# USB_mega.net
KiCad netlist of a schematic drawn in Altium Designer
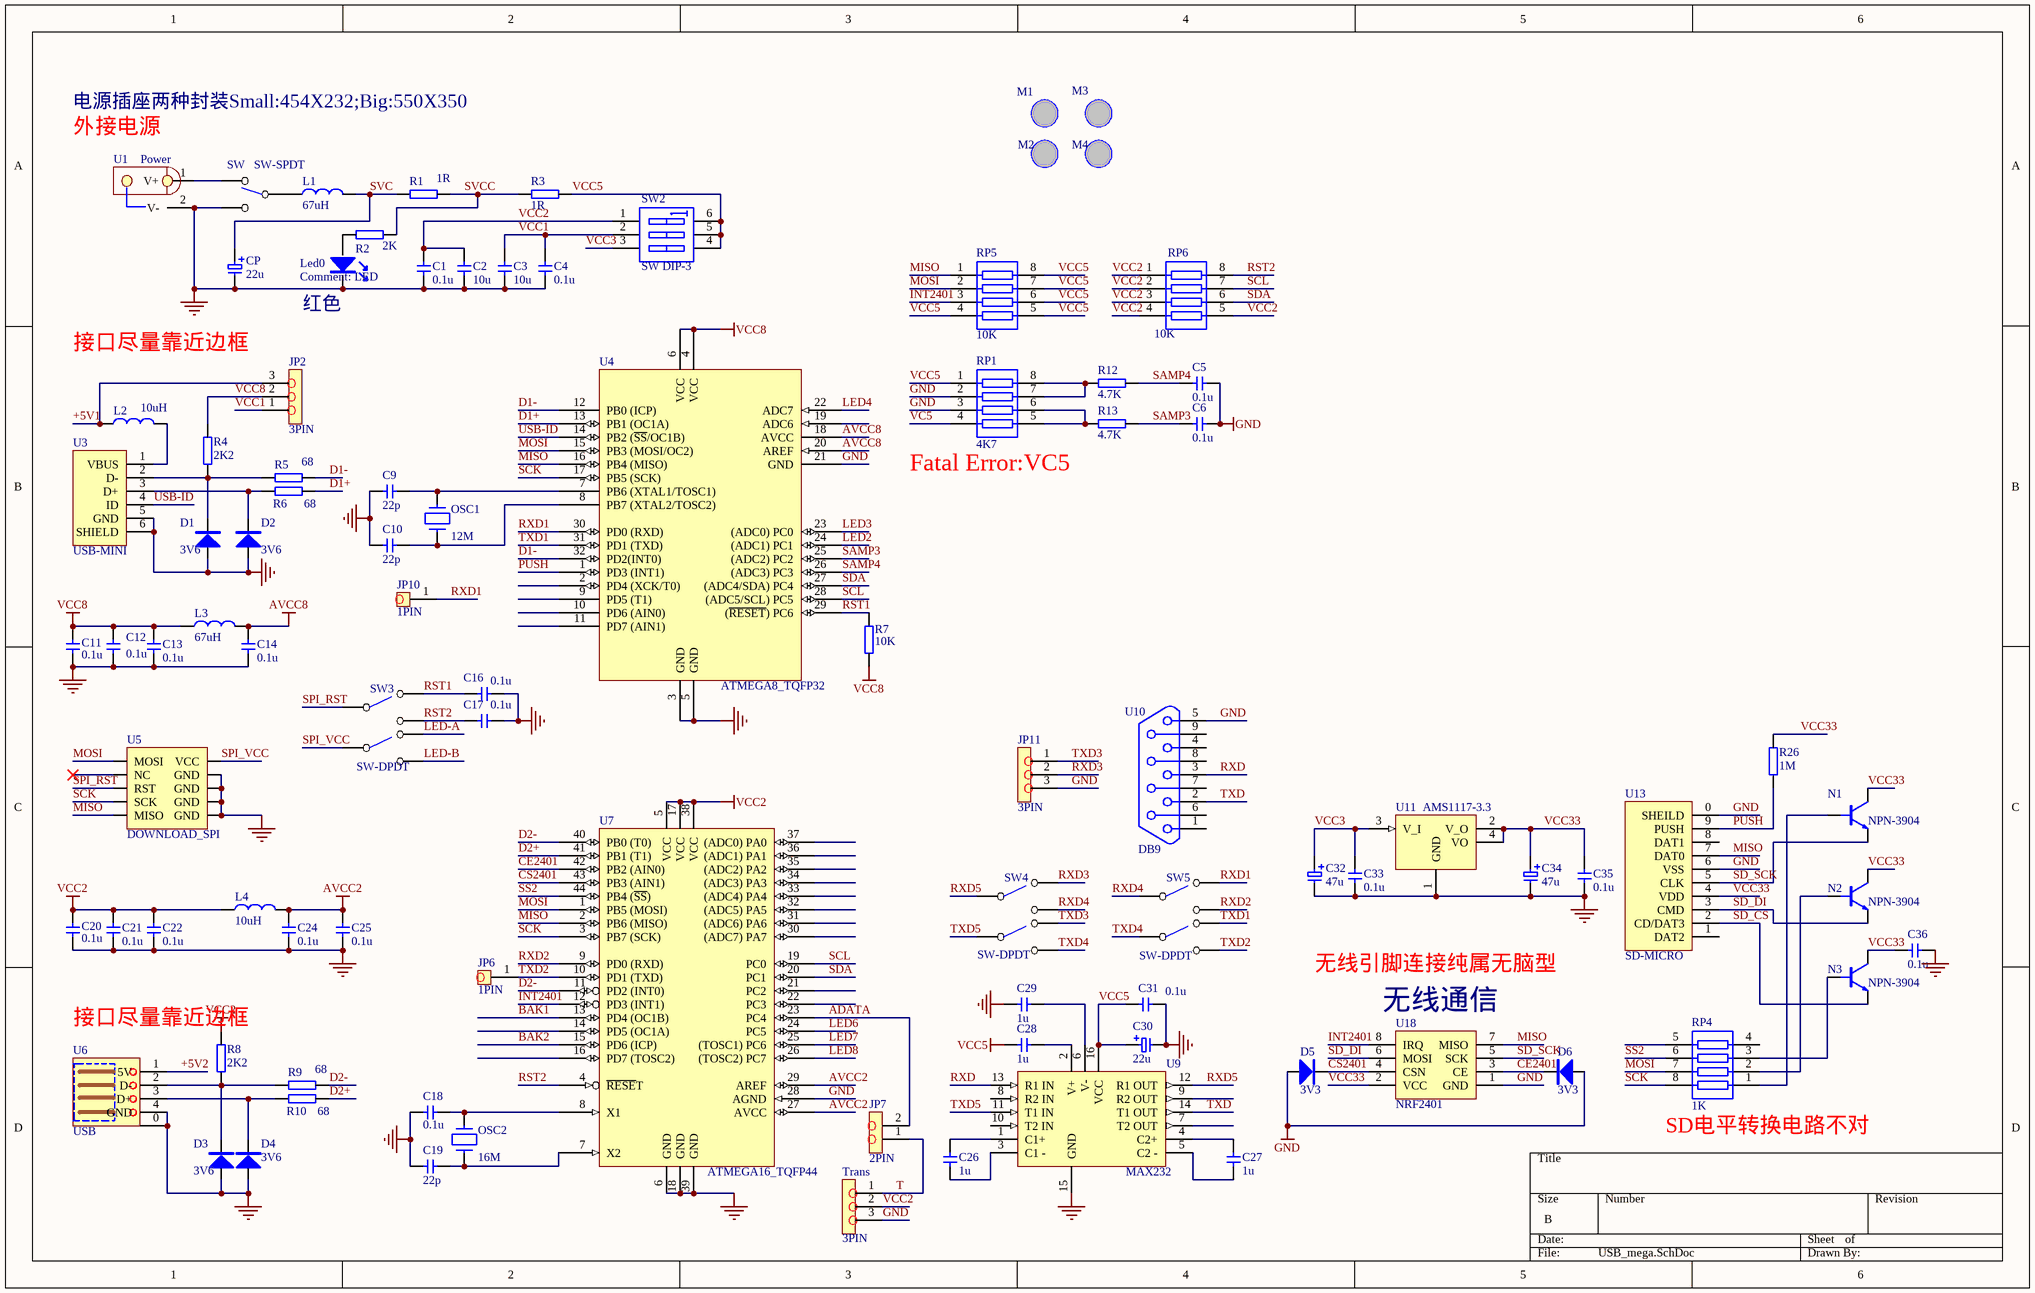
[diagram p0: USB_mega.SchDoc]

(export (version "E")
  (design (tool "Eeschema 10.0.6"))
  (components
    (comp (ref "C1") (value "0.1u") (footprint "0805") (libsource (lib "*") (part "CAPA")))
    (comp (ref "C2") (value "10u") (footprint "0805") (libsource (lib "*") (part "CAPA")))
    (comp (ref "C3") (value "10u") (footprint "0805") (libsource (lib "*") (part "CAPA")))
    (comp (ref "C4") (value "0.1u") (footprint "0805") (libsource (lib "*") (part "CAPA")))
    (comp (ref "C5") (value "0.1u") (footprint "RC100") (libsource (lib "*") (part "CAPA")))
    (comp (ref "C6") (value "0.1u") (footprint "RC100") (libsource (lib "*") (part "CAPA")))
    (comp (ref "C9") (value "22p") (footprint "RC80") (libsource (lib "*") (part "CAPA")))
    (comp (ref "C10") (value "22p") (footprint "RC80") (libsource (lib "*") (part "CAPA")))
    (comp (ref "C11") (value "0.1u") (footprint "0805") (libsource (lib "*") (part "CAPA")))
    (comp (ref "C12") (value "0.1u") (footprint "0805") (libsource (lib "*") (part "CAPA")))
    (comp (ref "C13") (value "0.1u") (footprint "0805") (libsource (lib "*") (part "CAPA")))
    (comp (ref "C14") (value "0.1u") (footprint "0805") (libsource (lib "*") (part "CAPA")))
    (comp (ref "C16") (value "0.1u") (footprint "0805") (libsource (lib "*") (part "CAPA")))
    (comp (ref "C17") (value "0.1u") (footprint "0805") (libsource (lib "*") (part "CAPA")))
    (comp (ref "C18") (value "0.1u") (footprint "RC80") (libsource (lib "*") (part "CAPA")))
    (comp (ref "C19") (value "22p") (footprint "RC80") (libsource (lib "*") (part "CAPA")))
    (comp (ref "C20") (value "0.1u") (footprint "0805") (libsource (lib "*") (part "CAPA")))
    (comp (ref "C21") (value "0.1u") (footprint "0805") (libsource (lib "*") (part "CAPA")))
    (comp (ref "C22") (value "0.1u") (footprint "0805") (libsource (lib "*") (part "CAPA")))
    (comp (ref "C24") (value "0.1u") (footprint "0805") (libsource (lib "*") (part "CAPA")))
    (comp (ref "C25") (value "0.1u") (footprint "0805") (libsource (lib "*") (part "CAPA")))
    (comp (ref "C26") (value "1u") (footprint "0805") (libsource (lib "*") (part "CAPA")))
    (comp (ref "C27") (value "1u") (footprint "0805") (libsource (lib "*") (part "CAPA")))
    (comp (ref "C28") (value "1u") (footprint "0805") (libsource (lib "*") (part "CAPA")))
    (comp (ref "C29") (value "1u") (footprint "0805") (libsource (lib "*") (part "CAPA")))
    (comp (ref "C30") (value "22u") (footprint "CP+140") (libsource (lib "*") (part "CAP+")))
    (comp (ref "C31") (value "0.1u") (footprint "0805") (libsource (lib "*") (part "CAPA")))
    (comp (ref "C32") (value "47u") (footprint "CP+140") (libsource (lib "*") (part "CAP+")))
    (comp (ref "C33") (value "0.1u") (footprint "0805") (libsource (lib "*") (part "CAPA")))
    (comp (ref "C34") (value "47u") (footprint "CP+140") (libsource (lib "*") (part "CAP+")))
    (comp (ref "C35") (value "0.1u") (footprint "0805") (libsource (lib "*") (part "CAPA")))
    (comp (ref "C36") (value "0.1u") (footprint "0805") (libsource (lib "*") (part "CAPA")))
    (comp (ref "CP") (value "22u") (footprint "CP+140") (libsource (lib "*") (part "CAP+")))
    (comp (ref "D1") (value "3V6") (footprint "DC140") (libsource (lib "*") (part "DIODE")))
    (comp (ref "D2") (value "3V6") (footprint "DC140") (libsource (lib "*") (part "DIODE")))
    (comp (ref "D3") (value "3V6") (footprint "DC140") (libsource (lib "*") (part "DIODE")))
    (comp (ref "D4") (value "3V6") (footprint "DC140") (libsource (lib "*") (part "DIODE")))
    (comp (ref "D5") (value "3V3") (footprint "DC200") (libsource (lib "*") (part "DIODE")))
    (comp (ref "D6") (value "3V3") (footprint "DC200") (libsource (lib "*") (part "DIODE")))
    (comp (ref "JP2") (value "3PIN") (footprint "SIP3") (libsource (lib "") (part "3PIN_1")))
    (comp (ref "JP6") (value "1PIN") (footprint "SIP1") (libsource (lib "*") (part "1PIN")))
    (comp (ref "JP7") (value "2PIN") (footprint "SIP2") (libsource (lib "*") (part "2PIN")))
    (comp (ref "JP10") (value "1PIN") (footprint "SIP1") (libsource (lib "*") (part "1PIN")))
    (comp (ref "JP11") (value "3PIN") (footprint "SIP3") (libsource (lib "*") (part "3PIN")))
    (comp (ref "L1") (value "67uH") (footprint "1206") (libsource (lib "*") (part "LH")))
    (comp (ref "L2") (value "10uH") (footprint "0805") (libsource (lib "*") (part "LH")))
    (comp (ref "L3") (value "67uH") (footprint "1206") (libsource (lib "*") (part "LH")))
    (comp (ref "L4") (value "10uH") (footprint "0805") (libsource (lib "*") (part "LH")))
    (comp (ref "Led0") (value "LED") (footprint "LED100") (libsource (lib "*") (part "LED")))
    (comp (ref "M1") (value "M3") (footprint "M3") (libsource (lib "*") (part "M3")))
    (comp (ref "M2") (value "M3") (footprint "M3") (libsource (lib "*") (part "M3")))
    (comp (ref "M3") (value "M3") (footprint "M3") (libsource (lib "*") (part "M3")))
    (comp (ref "M4") (value "M3") (footprint "M3") (libsource (lib "*") (part "M3")))
    (comp (ref "N1") (value "NPN-3904") (footprint "SOT-23A") (libsource (lib "*") (part "NPN-A")))
    (comp (ref "N2") (value "NPN-3904") (footprint "SOT-23A") (libsource (lib "*") (part "NPN-A")))
    (comp (ref "N3") (value "NPN-3904") (footprint "SOT-23A") (libsource (lib "*") (part "NPN-A")))
    (comp (ref "OSC1") (value "12M") (footprint "OSC200") (libsource (lib "*") (part "CRYSTAL")))
    (comp (ref "OSC2") (value "16M") (footprint "OSC200") (libsource (lib "*") (part "CRYSTAL")))
    (comp (ref "R1") (value "1R") (footprint "0805") (libsource (lib "*") (part "RES2A")))
    (comp (ref "R2") (value "2K") (footprint "0805") (libsource (lib "*") (part "RES2A")))
    (comp (ref "R3") (value "1R") (footprint "0805") (libsource (lib "*") (part "RES2A")))
    (comp (ref "R4") (value "2K2") (footprint "0805") (libsource (lib "*") (part "RES2A")))
    (comp (ref "R5") (value "68") (footprint "0805") (libsource (lib "*") (part "RES2A")))
    (comp (ref "R6") (value "68") (footprint "0805") (libsource (lib "*") (part "RES2A")))
    (comp (ref "R7") (value "10K") (footprint "0805") (libsource (lib "*") (part "RES2A")))
    (comp (ref "R8") (value "2K2") (footprint "0805") (libsource (lib "*") (part "RES2A")))
    (comp (ref "R9") (value "68") (footprint "0805") (libsource (lib "*") (part "RES2A")))
    (comp (ref "R10") (value "68") (footprint "0805") (libsource (lib "*") (part "RES2A")))
    (comp (ref "R12") (value "4.7K") (footprint "0805") (libsource (lib "*") (part "RES2A")))
    (comp (ref "R13") (value "4.7K") (footprint "0805") (libsource (lib "*") (part "RES2A")))
    (comp (ref "R26") (value "1M") (footprint "0805") (libsource (lib "*") (part "RES2A")))
    (comp (ref "RP1") (value "4K7") (footprint "RN4") (libsource (lib "*") (part "RESPACK4")))
    (comp (ref "RP4") (value "1K") (footprint "RN4") (libsource (lib "*") (part "RESPACK4")))
    (comp (ref "RP5") (value "10K") (footprint "RN4") (libsource (lib "*") (part "RESPACK4")))
    (comp (ref "RP6") (value "10K") (footprint "RN4") (libsource (lib "*") (part "RESPACK4")))
    (comp (ref "SW") (value "SW-SPDT") (footprint "SW-SPDT") (libsource (lib "*") (part "SW-SPDT")))
    (comp (ref "SW2")
      (value "SW DIP-3")
      (footprint "SW-DIP3")
      (description "DIP Switch")
      (libsource (lib "*") (part "SW DIP-3"))
    )
    (comp (ref "SW3") (value "SW-DPDT") (footprint "SW-DPDT") (libsource (lib "*") (part "SW-DPDT")))
    (comp (ref "SW4") (value "SW-DPDT") (footprint "SW-DPDT") (libsource (lib "*") (part "SW-DPDT")))
    (comp (ref "SW5") (value "SW-DPDT") (footprint "SW-DPDT") (libsource (lib "*") (part "SW-DPDT")))
    (comp (ref "Trans") (value "3PIN") (footprint "SIP3") (libsource (lib "*") (part "3PIN")))
    (comp (ref "U1") (value "Power") (footprint "POWER_BIG") (libsource (lib "*") (part "POWER")))
    (comp (ref "U3") (value "USB-MINI") (footprint "USB-MINI-R") (libsource (lib "*") (part "USB-MINI")))
    (comp (ref "U4")
      (value "ATMEGA8_TQFP32")
      (footprint "TQFP-32")
      (description "Atmel Microcontroller - Library created by carel..  <www.mpfreezone.com>")
      (libsource (lib "*") (part "ATMEGA8_TQFP32"))
    )
    (comp (ref "U5")
      (value "DOWNLOAD_SPI")
      (footprint "DOWNLOAD")
      (libsource (lib "*") (part "DOWNLOAD_SPI"))
    )
    (comp (ref "U6") (value "USB") (footprint "USB-A-R") (libsource (lib "*") (part "USB")))
    (comp (ref "U7")
      (value "ATMEGA16_TQFP44")
      (footprint "TQFP-44")
      (description "Atmel Microcontroller - Library created by carel..  <www.mpfreezone.com>")
      (libsource (lib "*") (part "AT90S8535_TQFP44"))
    )
    (comp (ref "U9") (value "MAX232") (footprint "SO-16") (libsource (lib "*") (part "MAX232")))
    (comp (ref "U10") (value "DB9") (footprint "DB-9RA/F") (libsource (lib "*") (part "DB9")))
    (comp (ref "U11") (value "AMS1117-3.3") (footprint "SOT-223") (libsource (lib "*") (part "VOTAGE_V33")))
    (comp (ref "U13") (value "SD-MICRO") (footprint "TF-2") (libsource (lib "*") (part "SD-MICRO")))
    (comp (ref "U18") (value "NRF2401") (footprint "NRF2401") (libsource (lib "*") (part "NRF2401")))
  )
  (nets
    (net (code "1") (name "/+5V1") (class "Default")
      (node (ref "JP2") (pin "3") (pintype "passive"))
      (node (ref "L2") (pin "1") (pintype "passive"))
    )
    (net (code "2") (name "/+5V2") (class "Default")
      (node (ref "U6") (pin "1") (pinfunction "5V_1") (pintype "passive"))
    )
    (net (code "4") (name "/ADATA") (class "Default")
      (node (ref "JP7") (pin "2") (pintype "passive"))
      (node (ref "U7") (pin "23") (pinfunction "PC4_23") (pintype "bidirectional"))
    )
    (net (code "5") (name "/BAK1") (class "Default")
      (node (ref "U7") (pin "13") (pinfunction "PD4_(OC1B)_13") (pintype "bidirectional"))
    )
    (net (code "6") (name "/BAK2") (class "Default")
      (node (ref "U7") (pin "15") (pinfunction "PD6_(ICP)_15") (pintype "bidirectional"))
    )
    (net (code "7") (name "/CE2401") (class "Default")
      (node (ref "D6") (pin "K") (pintype "passive"))
      (node (ref "U18") (pin "3") (pinfunction "CE_3") (pintype "passive"))
      (node (ref "U7") (pin "42") (pinfunction "PB2_(AIN0)_42") (pintype "bidirectional"))
    )
    (net (code "8") (name "/CS2401") (class "Default")
      (node (ref "D5") (pin "K") (pintype "passive"))
      (node (ref "U18") (pin "4") (pinfunction "CSN_4") (pintype "passive"))
      (node (ref "U7") (pin "43") (pinfunction "PB3_(AIN1)_43") (pintype "bidirectional"))
    )
    (net (code "9") (name "/D1+") (class "Default")
      (node (ref "R6") (pin "2") (pintype "passive"))
      (node (ref "U4") (pin "13") (pinfunction "PB1_(OC1A)_13") (pintype "bidirectional"))
    )
    (net (code "10") (name "/D1-") (class "Default")
      (node (ref "R5") (pin "2") (pintype "passive"))
      (node (ref "U4") (pin "12") (pinfunction "PB0_(ICP)_12") (pintype "passive"))
      (node (ref "U4") (pin "32") (pinfunction "PD2(INT0)_32") (pintype "bidirectional"))
    )
    (net (code "11") (name "/D2+") (class "Default")
      (node (ref "R10") (pin "2") (pintype "passive"))
      (node (ref "U7") (pin "41") (pinfunction "PB1_(T1)_41") (pintype "bidirectional"))
    )
    (net (code "12") (name "/D2-") (class "Default")
      (node (ref "R9") (pin "2") (pintype "passive"))
      (node (ref "U7") (pin "11") (pinfunction "PD2_(INT0)_11") (pintype "bidirectional"))
      (node (ref "U7") (pin "40") (pinfunction "PB0_(T0)_40") (pintype "bidirectional"))
    )
    (net (code "13") (name "/INT2401") (class "Default")
      (node (ref "RP5") (pin "3") (pintype "passive"))
      (node (ref "U18") (pin "8") (pinfunction "IRQ_8") (pintype "passive"))
      (node (ref "U7") (pin "12") (pinfunction "PD3_(INT1)_12") (pintype "bidirectional"))
    )
    (net (code "14") (name "/LED-A") (class "Default") (node (ref "SW3") (pin "5") (pintype "passive")))
    (net (code "15") (name "/LED-B") (class "Default") (node (ref "SW3") (pin "6") (pintype "passive")))
    (net (code "16") (name "/LED2") (class "Default")
      (node (ref "U4") (pin "24") (pinfunction "(ADC1)_PC1_24") (pintype "bidirectional"))
    )
    (net (code "17") (name "/LED3") (class "Default")
      (node (ref "U4") (pin "23") (pinfunction "(ADC0)_PC0_23") (pintype "bidirectional"))
    )
    (net (code "18") (name "/LED4") (class "Default")
      (node (ref "U4") (pin "22") (pinfunction "ADC7_22") (pintype "input"))
    )
    (net (code "19") (name "/LED6") (class "Default")
      (node (ref "U7") (pin "24") (pinfunction "PC5_24") (pintype "bidirectional"))
    )
    (net (code "20") (name "/LED7") (class "Default")
      (node (ref "U7") (pin "25") (pinfunction "(TOSC1)_PC6_25") (pintype "bidirectional"))
    )
    (net (code "21") (name "/LED8") (class "Default")
      (node (ref "U7") (pin "26") (pinfunction "(TOSC2)_PC7_26") (pintype "bidirectional"))
    )
    (net (code "22") (name "/MISO") (class "Default")
      (node (ref "RP5") (pin "1") (pintype "passive"))
      (node (ref "U13") (pin "7") (pinfunction "DAT0_7") (pintype "passive"))
      (node (ref "U18") (pin "7") (pinfunction "MISO_7") (pintype "passive"))
      (node (ref "U4") (pin "16") (pinfunction "PB4_(MISO)_16") (pintype "bidirectional"))
      (node (ref "U5") (pin "9") (pinfunction "MISO_9") (pintype "passive"))
      (node (ref "U7") (pin "2") (pinfunction "PB6_(MISO)_2") (pintype "bidirectional"))
    )
    (net (code "23") (name "/MOSI") (class "Default")
      (node (ref "RP4") (pin "7") (pintype "passive"))
      (node (ref "RP5") (pin "2") (pintype "passive"))
      (node (ref "U4") (pin "15") (pinfunction "PB3_(MOSI/OC2)_15") (pintype "bidirectional"))
      (node (ref "U5") (pin "1") (pinfunction "MOSI_1") (pintype "passive"))
      (node (ref "U7") (pin "1") (pinfunction "PB5_(MOSI)_1") (pintype "bidirectional"))
    )
    (net (code "24") (name "/PUSH") (class "Default")
      (node (ref "R26") (pin "1") (pintype "passive"))
      (node (ref "U13") (pin "9") (pinfunction "PUSH_9") (pintype "passive"))
      (node (ref "U4") (pin "1") (pinfunction "PD3_(INT1)_1") (pintype "bidirectional"))
    )
    (net (code "25") (name "/RST1") (class "Default")
      (node (ref "C16") (pin "2") (pintype "passive"))
      (node (ref "R7") (pin "1") (pintype "passive"))
      (node (ref "SW3") (pin "2") (pintype "passive"))
      (node (ref "U4") (pin "29") (pinfunction "(~{RESET})_PC6_29") (pintype "bidirectional"))
    )
    (net (code "26") (name "/RST2") (class "Default")
      (node (ref "C17") (pin "2") (pintype "passive"))
      (node (ref "RP6") (pin "8") (pintype "passive"))
      (node (ref "SW3") (pin "3") (pintype "passive"))
      (node (ref "U7") (pin "4") (pinfunction "~{RESE}T_4") (pintype "input"))
    )
    (net (code "27") (name "/RXD") (class "Default")
      (node (ref "U10") (pin "3") (pinfunction "3_3") (pintype "passive"))
      (node (ref "U9") (pin "13") (pinfunction "R1_IN_13") (pintype "input"))
    )
    (net (code "28") (name "/RXD1") (class "Default")
      (node (ref "JP10") (pin "1") (pintype "passive"))
      (node (ref "SW5") (pin "2") (pintype "passive"))
      (node (ref "U4") (pin "30") (pinfunction "PD0_(RXD)_30") (pintype "bidirectional"))
    )
    (net (code "29") (name "/RXD2") (class "Default")
      (node (ref "SW5") (pin "3") (pintype "passive"))
      (node (ref "U7") (pin "9") (pinfunction "PD0_(RXD)_9") (pintype "bidirectional"))
    )
    (net (code "30") (name "/RXD3") (class "Default")
      (node (ref "JP11") (pin "2") (pintype "passive"))
      (node (ref "SW4") (pin "2") (pintype "passive"))
    )
    (net (code "31") (name "/RXD4") (class "Default")
      (node (ref "SW4") (pin "3") (pintype "passive"))
      (node (ref "SW5") (pin "1") (pintype "passive"))
    )
    (net (code "32") (name "/RXD5") (class "Default")
      (node (ref "SW4") (pin "1") (pintype "passive"))
      (node (ref "U9") (pin "12") (pinfunction "R1_OUT_12") (pintype "output"))
    )
    (net (code "33") (name "/SAMP3") (class "Default")
      (node (ref "C6") (pin "1") (pintype "passive"))
      (node (ref "R13") (pin "2") (pintype "passive"))
      (node (ref "U4") (pin "25") (pinfunction "(ADC2)_PC2_25") (pintype "bidirectional"))
    )
    (net (code "34") (name "/SAMP4") (class "Default")
      (node (ref "C5") (pin "1") (pintype "passive"))
      (node (ref "R12") (pin "2") (pintype "passive"))
      (node (ref "U4") (pin "26") (pinfunction "(ADC3)_PC3_26") (pintype "bidirectional"))
    )
    (net (code "35") (name "/SCK") (class "Default")
      (node (ref "RP4") (pin "8") (pintype "passive"))
      (node (ref "U4") (pin "17") (pinfunction "PB5_(SCK)_17") (pintype "bidirectional"))
      (node (ref "U5") (pin "7") (pinfunction "SCK_7") (pintype "passive"))
      (node (ref "U7") (pin "3") (pinfunction "PB7_(SCK)_3") (pintype "bidirectional"))
    )
    (net (code "36") (name "/SCL") (class "Default")
      (node (ref "RP6") (pin "7") (pintype "passive"))
      (node (ref "U4") (pin "28") (pinfunction "(ADC5/SCL)_PC5_28") (pintype "bidirectional"))
      (node (ref "U7") (pin "19") (pinfunction "PC0_19") (pintype "bidirectional"))
    )
    (net (code "37") (name "/SDA") (class "Default")
      (node (ref "RP6") (pin "6") (pintype "passive"))
      (node (ref "U4") (pin "27") (pinfunction "(ADC4/SDA)_PC4_27") (pintype "bidirectional"))
      (node (ref "U7") (pin "20") (pinfunction "PC1_20") (pintype "bidirectional"))
    )
    (net (code "38") (name "/SD_CS") (class "Default")
      (node (ref "N3") (pin "E") (pintype "passive"))
      (node (ref "U13") (pin "2") (pinfunction "CD/DAT3_2") (pintype "passive"))
    )
    (net (code "39") (name "/SD_DI") (class "Default")
      (node (ref "N2") (pin "E") (pintype "passive"))
      (node (ref "U13") (pin "3") (pinfunction "CMD_3") (pintype "passive"))
      (node (ref "U18") (pin "6") (pinfunction "MOSI_6") (pintype "passive"))
    )
    (net (code "40") (name "/SD_SCK") (class "Default")
      (node (ref "N1") (pin "E") (pintype "passive"))
      (node (ref "U13") (pin "5") (pinfunction "CLK_5") (pintype "passive"))
      (node (ref "U18") (pin "5") (pinfunction "SCK_5") (pintype "passive"))
    )
    (net (code "41") (name "/SPI_RST") (class "Default")
      (node (ref "SW3") (pin "1") (pintype "passive"))
      (node (ref "U5") (pin "5") (pinfunction "RST_5") (pintype "passive"))
    )
    (net (code "42") (name "/SPI_VCC") (class "Default")
      (node (ref "SW3") (pin "4") (pintype "passive"))
      (node (ref "U5") (pin "2") (pinfunction "VCC_2") (pintype "passive"))
    )
    (net (code "43") (name "/SS2") (class "Default")
      (node (ref "RP4") (pin "6") (pintype "passive"))
      (node (ref "U7") (pin "44") (pinfunction "PB4_(~{SS})_44") (pintype "bidirectional"))
    )
    (net (code "44") (name "/SVC") (class "Default")
      (node (ref "CP") (pin "1") (pintype "passive"))
      (node (ref "L1") (pin "2") (pintype "passive"))
      (node (ref "R1") (pin "1") (pintype "passive"))
    )
    (net (code "45") (name "/SVCC") (class "Default")
      (node (ref "R1") (pin "2") (pintype "passive"))
      (node (ref "R2") (pin "1") (pintype "passive"))
      (node (ref "R3") (pin "1") (pintype "passive"))
    )
    (net (code "46") (name "/T") (class "Default")
      (node (ref "JP7") (pin "1") (pintype "passive"))
      (node (ref "Trans") (pin "1") (pintype "passive"))
    )
    (net (code "47") (name "/TXD") (class "Default")
      (node (ref "U10") (pin "2") (pinfunction "2_2") (pintype "passive"))
      (node (ref "U9") (pin "14") (pinfunction "T1_OUT_14") (pintype "output"))
    )
    (net (code "48") (name "/TXD1") (class "Default")
      (node (ref "SW5") (pin "5") (pintype "passive"))
      (node (ref "U4") (pin "31") (pinfunction "PD1_(TXD)_31") (pintype "bidirectional"))
    )
    (net (code "49") (name "/TXD2") (class "Default")
      (node (ref "JP6") (pin "1") (pintype "passive"))
      (node (ref "SW5") (pin "6") (pintype "passive"))
      (node (ref "U7") (pin "10") (pinfunction "PD1_(TXD)_10") (pintype "bidirectional"))
    )
    (net (code "50") (name "/TXD3") (class "Default")
      (node (ref "JP11") (pin "1") (pintype "passive"))
      (node (ref "SW4") (pin "5") (pintype "passive"))
    )
    (net (code "51") (name "/TXD4") (class "Default")
      (node (ref "SW4") (pin "6") (pintype "passive"))
      (node (ref "SW5") (pin "4") (pintype "passive"))
    )
    (net (code "52") (name "/TXD5") (class "Default")
      (node (ref "SW4") (pin "4") (pintype "passive"))
      (node (ref "U9") (pin "11") (pinfunction "T1_IN_11") (pintype "input"))
    )
    (net (code "53") (name "/USB-ID") (class "Default")
      (node (ref "U3") (pin "4") (pinfunction "ID_4") (pintype "passive"))
      (node (ref "U4") (pin "14") (pinfunction "PB2_(~{SS}/OC1B)_14") (pintype "bidirectional"))
    )
    (net (code "54") (name "/VC5") (class "Default") (node (ref "RP1") (pin "4") (pintype "passive")))
    (net (code "55") (name "/VCC1") (class "Default")
      (node (ref "C3") (pin "2") (pintype "passive"))
      (node (ref "C4") (pin "2") (pintype "passive"))
      (node (ref "JP2") (pin "1") (pintype "passive"))
      (node (ref "SW2") (pin "2") (pinfunction "A2_2") (pintype "passive"))
    )
    (net (code "56") (name "/VCC3") (class "Default")
      (node (ref "C32") (pin "1") (pintype "passive"))
      (node (ref "C33") (pin "1") (pintype "passive"))
      (node (ref "SW2") (pin "3") (pinfunction "A3_3") (pintype "passive"))
      (node (ref "U11") (pin "3") (pinfunction "V_I_3") (pintype "input"))
    )
    (net (code "57") (name "/VCC33") (class "Default")
      (node (ref "C34") (pin "1") (pintype "passive"))
      (node (ref "C35") (pin "1") (pintype "passive"))
      (node (ref "C36") (pin "1") (pintype "passive"))
      (node (ref "N1") (pin "C") (pintype "passive"))
      (node (ref "N2") (pin "C") (pintype "passive"))
      (node (ref "N3") (pin "C") (pintype "passive"))
      (node (ref "R26") (pin "2") (pintype "passive"))
      (node (ref "U11") (pin "2") (pinfunction "V_O_2") (pintype "power_in"))
      (node (ref "U11") (pin "4") (pinfunction "VO_4") (pintype "passive"))
      (node (ref "U13") (pin "4") (pinfunction "VDD_4") (pintype "passive"))
      (node (ref "U18") (pin "2") (pinfunction "VCC_2") (pintype "passive"))
    )
    (net (code "58") (name "AVCC2") (class "Default")
      (node (ref "C24") (pin "1") (pintype "passive"))
      (node (ref "C25") (pin "1") (pintype "passive"))
      (node (ref "L4") (pin "2") (pintype "passive"))
      (node (ref "U7") (pin "27") (pinfunction "AVCC_27") (pintype "bidirectional"))
      (node (ref "U7") (pin "29") (pinfunction "AREF_29") (pintype "bidirectional"))
    )
    (net (code "59") (name "AVCC8") (class "Default")
      (node (ref "C14") (pin "1") (pintype "passive"))
      (node (ref "L3") (pin "2") (pintype "passive"))
      (node (ref "U4") (pin "18") (pinfunction "AVCC_18") (pintype "passive"))
      (node (ref "U4") (pin "20") (pinfunction "AREF_20") (pintype "input"))
    )
    (net (code "60") (name "GND") (class "Default")
      (node (ref "C1") (pin "1") (pintype "passive"))
      (node (ref "C10") (pin "1") (pintype "passive"))
      (node (ref "C11") (pin "2") (pintype "passive"))
      (node (ref "C12") (pin "2") (pintype "passive"))
      (node (ref "C13") (pin "2") (pintype "passive"))
      (node (ref "C14") (pin "2") (pintype "passive"))
      (node (ref "C16") (pin "1") (pintype "passive"))
      (node (ref "C17") (pin "1") (pintype "passive"))
      (node (ref "C18") (pin "1") (pintype "passive"))
      (node (ref "C19") (pin "1") (pintype "passive"))
      (node (ref "C2") (pin "1") (pintype "passive"))
      (node (ref "C20") (pin "1") (pintype "passive"))
      (node (ref "C21") (pin "1") (pintype "passive"))
      (node (ref "C22") (pin "2") (pintype "passive"))
      (node (ref "C24") (pin "2") (pintype "passive"))
      (node (ref "C25") (pin "2") (pintype "passive"))
      (node (ref "C29") (pin "1") (pintype "passive"))
      (node (ref "C3") (pin "1") (pintype "passive"))
      (node (ref "C30") (pin "2") (pintype "passive"))
      (node (ref "C31") (pin "2") (pintype "passive"))
      (node (ref "C32") (pin "2") (pintype "passive"))
      (node (ref "C33") (pin "2") (pintype "passive"))
      (node (ref "C34") (pin "2") (pintype "passive"))
      (node (ref "C35") (pin "2") (pintype "passive"))
      (node (ref "C36") (pin "2") (pintype "passive"))
      (node (ref "C4") (pin "1") (pintype "passive"))
      (node (ref "C5") (pin "2") (pintype "passive"))
      (node (ref "C6") (pin "2") (pintype "passive"))
      (node (ref "C9") (pin "1") (pintype "passive"))
      (node (ref "CP") (pin "2") (pintype "passive"))
      (node (ref "D1") (pin "A") (pintype "passive"))
      (node (ref "D2") (pin "A") (pintype "passive"))
      (node (ref "D3") (pin "A") (pintype "passive"))
      (node (ref "D4") (pin "A") (pintype "passive"))
      (node (ref "D5") (pin "A") (pintype "passive"))
      (node (ref "D6") (pin "A") (pintype "passive"))
      (node (ref "JP11") (pin "3") (pintype "passive"))
      (node (ref "Led0") (pin "K") (pintype "passive"))
      (node (ref "RP1") (pin "2") (pintype "passive"))
      (node (ref "RP1") (pin "3") (pintype "passive"))
      (node (ref "SW") (pin "1") (pintype "passive"))
      (node (ref "Trans") (pin "3") (pintype "passive"))
      (node (ref "U1") (pin "2") (pinfunction "V-_2") (pintype "passive"))
      (node (ref "U10") (pin "5") (pinfunction "5_5") (pintype "passive"))
      (node (ref "U11") (pin "1") (pinfunction "GND_1") (pintype "power_in"))
      (node (ref "U13") (pin "0") (pinfunction "SHEILD_0") (pintype "passive"))
      (node (ref "U13") (pin "6") (pinfunction "VSS_6") (pintype "passive"))
      (node (ref "U18") (pin "1") (pinfunction "GND_1") (pintype "passive"))
      (node (ref "U3") (pin "5") (pinfunction "GND_5") (pintype "passive"))
      (node (ref "U3") (pin "6") (pinfunction "SHIELD_6") (pintype "passive"))
      (node (ref "U4") (pin "21") (pinfunction "GND_21") (pintype "passive"))
      (node (ref "U4") (pin "3") (pinfunction "GND_3") (pintype "passive"))
      (node (ref "U4") (pin "5") (pinfunction "GND_5") (pintype "power_in"))
      (node (ref "U5") (pin "10") (pinfunction "GND_10") (pintype "passive"))
      (node (ref "U5") (pin "4") (pinfunction "GND_4") (pintype "passive"))
      (node (ref "U5") (pin "6") (pinfunction "GND_6") (pintype "passive"))
      (node (ref "U5") (pin "8") (pinfunction "GND_8") (pintype "passive"))
      (node (ref "U6") (pin "0") (pintype "passive"))
      (node (ref "U6") (pin "4") (pinfunction "GND_4") (pintype "power_in"))
      (node (ref "U7") (pin "18") (pinfunction "GND_18") (pintype "passive"))
      (node (ref "U7") (pin "28") (pinfunction "AGND_28") (pintype "input"))
      (node (ref "U7") (pin "39") (pinfunction "GND_39") (pintype "power_in"))
      (node (ref "U7") (pin "6") (pinfunction "GND_6") (pintype "passive"))
      (node (ref "U9") (pin "15") (pinfunction "GND_15") (pintype "power_in"))
    )
    (net (code "61") (name "Net-(L1-Pad1)") (class "Default")
      (node (ref "L1") (pin "1") (pintype "passive"))
      (node (ref "SW") (pin "2") (pintype "passive"))
    )
    (net (code "62") (name "Net-(Led0-PadA)") (class "Default")
      (node (ref "Led0") (pin "A") (pintype "passive"))
      (node (ref "R2") (pin "2") (pintype "passive"))
    )
    (net (code "63") (name "Net-(N1-PadB)") (class "Default")
      (node (ref "N1") (pin "B") (pintype "passive"))
      (node (ref "RP4") (pin "1") (pintype "passive"))
    )
    (net (code "64") (name "Net-(N2-PadB)") (class "Default")
      (node (ref "N2") (pin "B") (pintype "passive"))
      (node (ref "RP4") (pin "2") (pintype "passive"))
    )
    (net (code "65") (name "Net-(N3-PadB)") (class "Default")
      (node (ref "N3") (pin "B") (pintype "passive"))
      (node (ref "RP4") (pin "3") (pintype "passive"))
    )
    (net (code "66") (name "Net-(R12-Pad1)") (class "Default")
      (node (ref "R12") (pin "1") (pintype "passive"))
      (node (ref "RP1") (pin "7") (pintype "passive"))
      (node (ref "RP1") (pin "8") (pintype "passive"))
    )
    (net (code "67") (name "Net-(R13-Pad1)") (class "Default")
      (node (ref "R13") (pin "1") (pintype "passive"))
      (node (ref "RP1") (pin "5") (pintype "passive"))
      (node (ref "RP1") (pin "6") (pintype "passive"))
    )
    (net (code "68") (name "Net-(U1-V+)") (class "Default")
      (node (ref "SW") (pin "3") (pintype "passive"))
      (node (ref "U1") (pin "1") (pinfunction "V+_1") (pintype "passive"))
    )
    (net (code "69") (name "Net-(U3-D+)") (class "Default")
      (node (ref "D2") (pin "K") (pintype "passive"))
      (node (ref "R6") (pin "1") (pintype "passive"))
      (node (ref "U3") (pin "3") (pinfunction "D+_3") (pintype "passive"))
    )
    (net (code "70") (name "Net-(U3-D-)") (class "Default")
      (node (ref "D1") (pin "K") (pintype "passive"))
      (node (ref "R4") (pin "1") (pintype "passive"))
      (node (ref "R5") (pin "1") (pintype "passive"))
      (node (ref "U3") (pin "2") (pinfunction "D-_2") (pintype "passive"))
    )
    (net (code "71") (name "Net-(U3-VBUS)") (class "Default")
      (node (ref "L2") (pin "2") (pintype "passive"))
      (node (ref "U3") (pin "1") (pinfunction "VBUS_1") (pintype "passive"))
    )
    (net (code "72") (name "Net-(U4-PB6_(XTAL1{slash}TOSC1))") (class "Default")
      (node (ref "C9") (pin "2") (pintype "passive"))
      (node (ref "OSC1") (pin "2") (pintype "passive"))
      (node (ref "U4") (pin "7") (pinfunction "PB6_(XTAL1/TOSC1)_7") (pintype "passive"))
    )
    (net (code "73") (name "Net-(U4-PB7_(XTAL2{slash}TOSC2))") (class "Default")
      (node (ref "C10") (pin "2") (pintype "passive"))
      (node (ref "OSC1") (pin "1") (pintype "passive"))
      (node (ref "U4") (pin "8") (pinfunction "PB7_(XTAL2/TOSC2)_8") (pintype "passive"))
    )
    (net (code "74") (name "Net-(U6-D+)") (class "Default")
      (node (ref "D4") (pin "K") (pintype "passive"))
      (node (ref "R10") (pin "1") (pintype "passive"))
      (node (ref "U6") (pin "3") (pinfunction "D+_3") (pintype "passive"))
    )
    (net (code "75") (name "Net-(U6-D-)") (class "Default")
      (node (ref "D3") (pin "K") (pintype "passive"))
      (node (ref "R8") (pin "1") (pintype "passive"))
      (node (ref "R9") (pin "1") (pintype "passive"))
      (node (ref "U6") (pin "2") (pinfunction "D-_2") (pintype "passive"))
    )
    (net (code "76") (name "Net-(U7-X1)") (class "Default")
      (node (ref "C18") (pin "2") (pintype "passive"))
      (node (ref "OSC2") (pin "2") (pintype "passive"))
      (node (ref "U7") (pin "8") (pinfunction "X1_8") (pintype "input"))
    )
    (net (code "77") (name "Net-(U7-X2)") (class "Default")
      (node (ref "C19") (pin "2") (pintype "passive"))
      (node (ref "OSC2") (pin "1") (pintype "passive"))
      (node (ref "U7") (pin "7") (pinfunction "X2_7") (pintype "input"))
    )
    (net (code "78") (name "Net-(U9-C1+)") (class "Default")
      (node (ref "C26") (pin "1") (pintype "passive"))
      (node (ref "U9") (pin "1") (pinfunction "C1+_1") (pintype "passive"))
    )
    (net (code "79") (name "Net-(U9-C1_-)") (class "Default")
      (node (ref "C26") (pin "2") (pintype "passive"))
      (node (ref "U9") (pin "3") (pinfunction "C1_-_3") (pintype "passive"))
    )
    (net (code "80") (name "Net-(U9-C2+)") (class "Default")
      (node (ref "C27") (pin "1") (pintype "passive"))
      (node (ref "U9") (pin "4") (pinfunction "C2+_4") (pintype "passive"))
    )
    (net (code "81") (name "Net-(U9-C2_-)") (class "Default")
      (node (ref "C27") (pin "2") (pintype "passive"))
      (node (ref "U9") (pin "5") (pinfunction "C2_-_5") (pintype "passive"))
    )
    (net (code "82") (name "Net-(U9-V+)") (class "Default")
      (node (ref "C28") (pin "2") (pintype "passive"))
      (node (ref "U9") (pin "2") (pinfunction "V+_2") (pintype "power_in"))
    )
    (net (code "83") (name "Net-(U9-V-)") (class "Default")
      (node (ref "C29") (pin "2") (pintype "passive"))
      (node (ref "U9") (pin "6") (pinfunction "V-_6") (pintype "power_in"))
    )
    (net (code "84") (name "VCC2") (class "Default")
      (node (ref "C1") (pin "2") (pintype "passive"))
      (node (ref "C2") (pin "2") (pintype "passive"))
      (node (ref "C20") (pin "2") (pintype "passive"))
      (node (ref "C21") (pin "2") (pintype "passive"))
      (node (ref "C22") (pin "1") (pintype "passive"))
      (node (ref "L4") (pin "1") (pintype "passive"))
      (node (ref "R8") (pin "2") (pintype "passive"))
      (node (ref "RP6") (pin "1") (pintype "passive"))
      (node (ref "RP6") (pin "2") (pintype "passive"))
      (node (ref "RP6") (pin "3") (pintype "passive"))
      (node (ref "RP6") (pin "4") (pintype "passive"))
      (node (ref "RP6") (pin "5") (pintype "passive"))
      (node (ref "SW2") (pin "1") (pinfunction "A1_1") (pintype "passive"))
      (node (ref "Trans") (pin "2") (pintype "passive"))
      (node (ref "U7") (pin "17") (pinfunction "VCC_17") (pintype "passive"))
      (node (ref "U7") (pin "38") (pinfunction "VCC_38") (pintype "power_in"))
      (node (ref "U7") (pin "5") (pinfunction "VCC_5") (pintype "passive"))
    )
    (net (code "85") (name "VCC5") (class "Default")
      (node (ref "C28") (pin "1") (pintype "passive"))
      (node (ref "C30") (pin "1") (pintype "passive"))
      (node (ref "C31") (pin "1") (pintype "passive"))
      (node (ref "R3") (pin "2") (pintype "passive"))
      (node (ref "RP1") (pin "1") (pintype "passive"))
      (node (ref "RP5") (pin "4") (pintype "passive"))
      (node (ref "RP5") (pin "5") (pintype "passive"))
      (node (ref "RP5") (pin "6") (pintype "passive"))
      (node (ref "RP5") (pin "7") (pintype "passive"))
      (node (ref "RP5") (pin "8") (pintype "passive"))
      (node (ref "SW2") (pin "4") (pinfunction "B3_4") (pintype "passive"))
      (node (ref "SW2") (pin "5") (pinfunction "B2_5") (pintype "passive"))
      (node (ref "SW2") (pin "6") (pinfunction "B1_6") (pintype "passive"))
      (node (ref "U9") (pin "16") (pinfunction "VCC_16") (pintype "power_in"))
    )
    (net (code "86") (name "VCC8") (class "Default")
      (node (ref "C11") (pin "1") (pintype "passive"))
      (node (ref "C12") (pin "1") (pintype "passive"))
      (node (ref "C13") (pin "1") (pintype "passive"))
      (node (ref "JP2") (pin "2") (pintype "passive"))
      (node (ref "L3") (pin "1") (pintype "passive"))
      (node (ref "R4") (pin "2") (pintype "passive"))
      (node (ref "R7") (pin "2") (pintype "passive"))
      (node (ref "U4") (pin "4") (pinfunction "VCC_4") (pintype "power_in"))
      (node (ref "U4") (pin "6") (pinfunction "VCC_6") (pintype "passive"))
    )
    (net (code "87") (name "unconnected-(RP4-Pad4)") (class "Default")
      (node (ref "RP4") (pin "4") (pintype "passive"))
    )
    (net (code "88") (name "unconnected-(RP4-Pad5)") (class "Default")
      (node (ref "RP4") (pin "5") (pintype "passive"))
    )
    (net (code "89") (name "unconnected-(U4-ADC6-Pad19)") (class "Default")
      (node (ref "U4") (pin "19") (pinfunction "ADC6_19") (pintype "input"))
    )
    (net (code "90") (name "unconnected-(U4-PD4_(XCK{slash}T0)-Pad2)") (class "Default")
      (node (ref "U4") (pin "2") (pinfunction "PD4_(XCK/T0)_2") (pintype "bidirectional"))
    )
    (net (code "91") (name "unconnected-(U4-PD5_(T1)-Pad9)") (class "Default")
      (node (ref "U4") (pin "9") (pinfunction "PD5_(T1)_9") (pintype "passive"))
    )
    (net (code "92") (name "unconnected-(U4-PD6_(AIN0)-Pad10)") (class "Default")
      (node (ref "U4") (pin "10") (pinfunction "PD6_(AIN0)_10") (pintype "passive"))
    )
    (net (code "93") (name "unconnected-(U4-PD7_(AIN1)-Pad11)") (class "Default")
      (node (ref "U4") (pin "11") (pinfunction "PD7_(AIN1)_11") (pintype "passive"))
    )
    (net (code "94") (name "unconnected-(U5-NC-Pad3)") (class "Default")
      (node (ref "U5") (pin "3") (pinfunction "NC_3") (pintype "passive+no_connect"))
    )
    (net (code "95") (name "unconnected-(U7-(ADC0)_PA0-Pad37)") (class "Default")
      (node (ref "U7") (pin "37") (pinfunction "(ADC0)_PA0_37") (pintype "bidirectional"))
    )
    (net (code "96") (name "unconnected-(U7-(ADC1)_PA1-Pad36)") (class "Default")
      (node (ref "U7") (pin "36") (pinfunction "(ADC1)_PA1_36") (pintype "bidirectional"))
    )
    (net (code "97") (name "unconnected-(U7-(ADC2)_PA2-Pad35)") (class "Default")
      (node (ref "U7") (pin "35") (pinfunction "(ADC2)_PA2_35") (pintype "bidirectional"))
    )
    (net (code "98") (name "unconnected-(U7-(ADC3)_PA3-Pad34)") (class "Default")
      (node (ref "U7") (pin "34") (pinfunction "(ADC3)_PA3_34") (pintype "bidirectional"))
    )
    (net (code "99") (name "unconnected-(U7-(ADC4)_PA4-Pad33)") (class "Default")
      (node (ref "U7") (pin "33") (pinfunction "(ADC4)_PA4_33") (pintype "bidirectional"))
    )
    (net (code "100") (name "unconnected-(U7-(ADC5)_PA5-Pad32)") (class "Default")
      (node (ref "U7") (pin "32") (pinfunction "(ADC5)_PA5_32") (pintype "bidirectional"))
    )
    (net (code "101") (name "unconnected-(U7-(ADC6)_PA6-Pad31)") (class "Default")
      (node (ref "U7") (pin "31") (pinfunction "(ADC6)_PA6_31") (pintype "bidirectional"))
    )
    (net (code "102") (name "unconnected-(U7-(ADC7)_PA7-Pad30)") (class "Default")
      (node (ref "U7") (pin "30") (pinfunction "(ADC7)_PA7_30") (pintype "bidirectional"))
    )
    (net (code "103") (name "unconnected-(U7-PC2-Pad21)") (class "Default")
      (node (ref "U7") (pin "21") (pinfunction "PC2_21") (pintype "bidirectional"))
    )
    (net (code "104") (name "unconnected-(U7-PC3-Pad22)") (class "Default")
      (node (ref "U7") (pin "22") (pinfunction "PC3_22") (pintype "bidirectional"))
    )
    (net (code "105") (name "unconnected-(U7-PD5_(OC1A)-Pad14)") (class "Default")
      (node (ref "U7") (pin "14") (pinfunction "PD5_(OC1A)_14") (pintype "bidirectional"))
    )
    (net (code "106") (name "unconnected-(U7-PD7_(TOSC2)-Pad16)") (class "Default")
      (node (ref "U7") (pin "16") (pinfunction "PD7_(TOSC2)_16") (pintype "bidirectional"))
    )
    (net (code "107") (name "unconnected-(U9-R2_IN-Pad8)") (class "Default")
      (node (ref "U9") (pin "8") (pinfunction "R2_IN_8") (pintype "input"))
    )
    (net (code "108") (name "unconnected-(U9-R2_OUT-Pad9)") (class "Default")
      (node (ref "U9") (pin "9") (pinfunction "R2_OUT_9") (pintype "output"))
    )
    (net (code "109") (name "unconnected-(U9-T2_IN-Pad10)") (class "Default")
      (node (ref "U9") (pin "10") (pinfunction "T2_IN_10") (pintype "input"))
    )
    (net (code "110") (name "unconnected-(U9-T2_OUT-Pad7)") (class "Default")
      (node (ref "U9") (pin "7") (pinfunction "T2_OUT_7") (pintype "output"))
    )
    (net (code "111") (name "unconnected-(U10-Pad1)") (class "Default")
      (node (ref "U10") (pin "1") (pinfunction "1_1") (pintype "passive"))
    )
    (net (code "112") (name "unconnected-(U10-Pad4)") (class "Default")
      (node (ref "U10") (pin "4") (pinfunction "4_4") (pintype "passive"))
    )
    (net (code "113") (name "unconnected-(U10-Pad6)") (class "Default")
      (node (ref "U10") (pin "6") (pinfunction "6_6") (pintype "passive"))
    )
    (net (code "114") (name "unconnected-(U10-Pad7)") (class "Default")
      (node (ref "U10") (pin "7") (pinfunction "7_7") (pintype "passive"))
    )
    (net (code "115") (name "unconnected-(U10-Pad8)") (class "Default")
      (node (ref "U10") (pin "8") (pinfunction "8_8") (pintype "passive"))
    )
    (net (code "116") (name "unconnected-(U10-Pad9)") (class "Default")
      (node (ref "U10") (pin "9") (pinfunction "9_9") (pintype "passive"))
    )
    (net (code "117") (name "unconnected-(U13-DAT1-Pad8)") (class "Default")
      (node (ref "U13") (pin "8") (pinfunction "DAT1_8") (pintype "passive"))
    )
    (net (code "118") (name "unconnected-(U13-DAT2-Pad1)") (class "Default")
      (node (ref "U13") (pin "1") (pinfunction "DAT2_1") (pintype "passive"))
    )
  )
)
